# P05_POWER02.net
KiCad netlist of a schematic drawn in Altium Designer
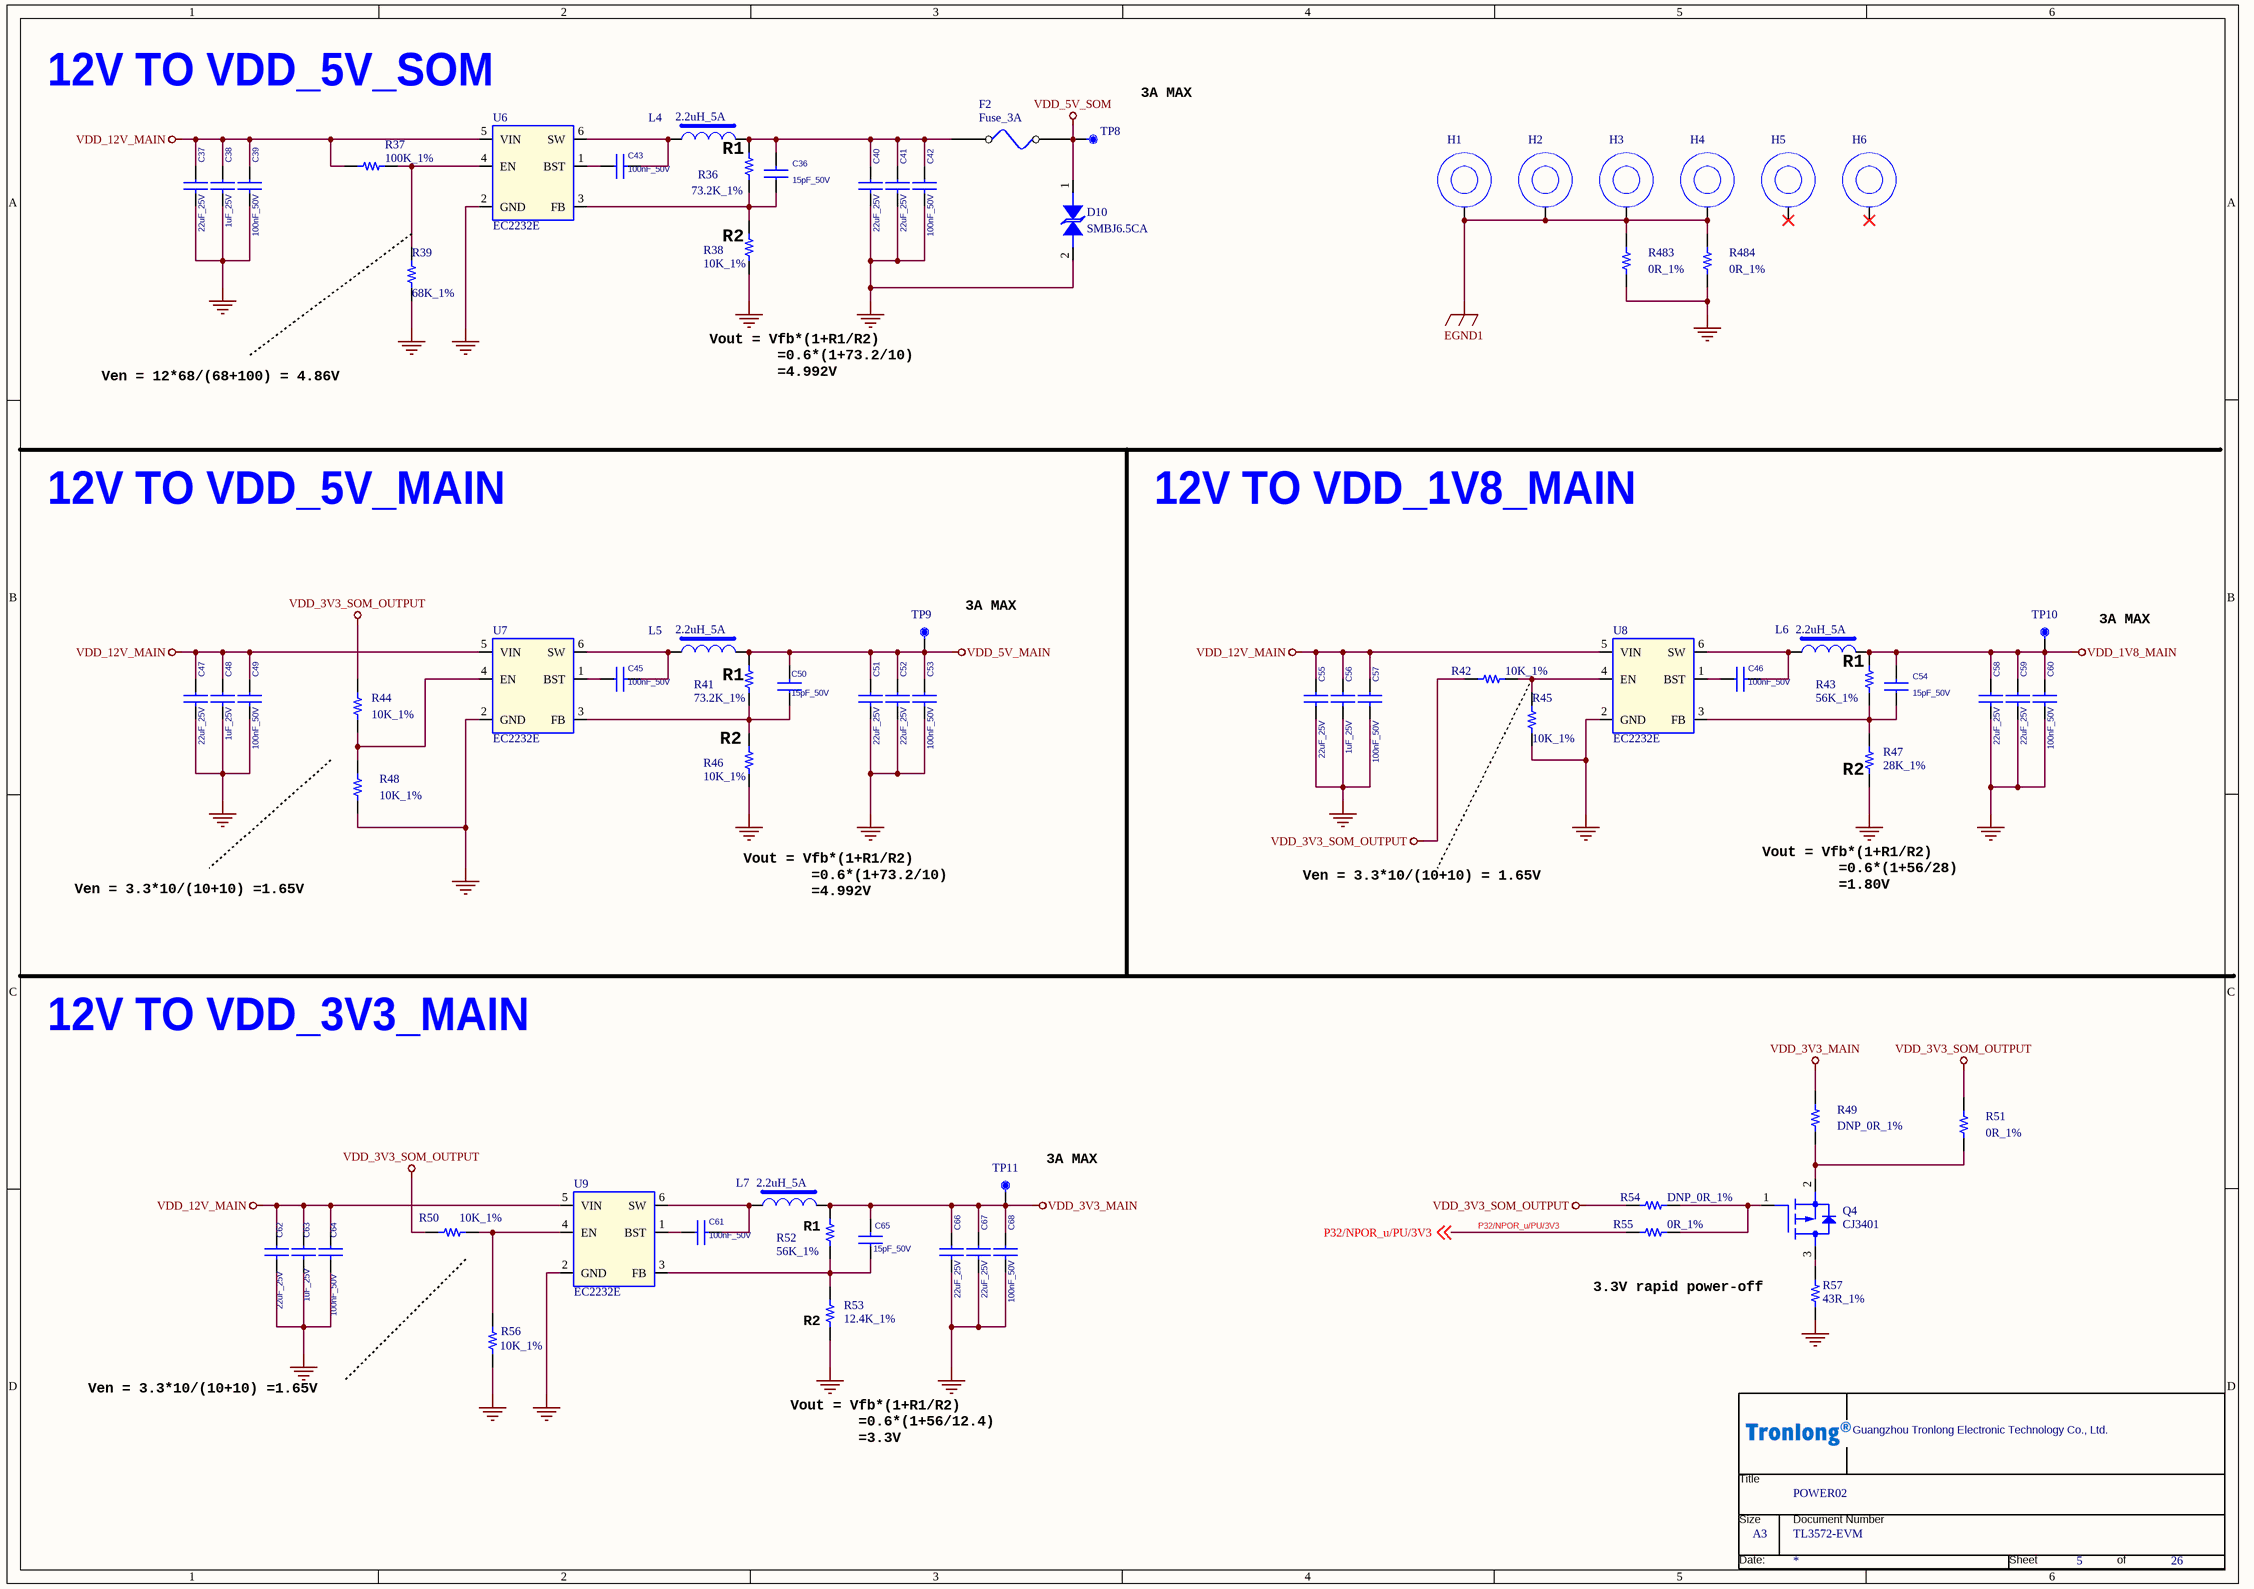
[diagram p0: P05_POWER02.SchDoc]

(export (version "E")
  (design (tool "Eeschema 10.0.6"))
  (components
    (comp (ref "C36")
      (value "15pF_50V")
      (footprint "C0603")
      (description "CL10C150JB8NNNC,CC0603JRNPO9BN150")
      (fields
        (field (name "MANUFACTURER") "广州创龙")
        (field (name "MANUFACTURER PARTNUMBER") "15pF,5%,C0603,50V,（X7R,X5R,COG,NPO或X7S）")
      )
      (libsource (lib "*") (part "CAP NP_Dup2"))
    )
    (comp (ref "C37")
      (value "22uF_25V")
      (footprint "C0805")
      (description "贴片陶瓷电容,22uF,20%,25V,X5R")
      (fields
        (field (name "MANUFACTURER") "广东风华高新科技股份有限公司（FH）")
        (field (name "MANUFACTURER PARTNUMBER") "0805X226M250NT")
      )
      (libsource (lib "*") (part "CAP NP_Dup2"))
    )
    (comp (ref "C38")
      (value "1uF_25V")
      (footprint "C0402")
      (description "贴片陶瓷电容,1uF,10%,25V,X5R")
      (fields
        (field (name "MANUFACTURER PARTNUMBER") "0402X105K250NT")
        (field (name "MANUFACTURER") "广东风华高新科技股份有限公司（FH）")
      )
      (libsource (lib "*") (part "CAP NP_Dup2"))
    )
    (comp (ref "C39")
      (value "100nF_50V")
      (footprint "C0402")
      (description "贴片陶瓷电容,100nF,10%,50V,X7R")
      (fields
        (field (name "MANUFACTURER") "广东风华高新科技股份有限公司（FH）")
        (field (name "MANUFACTURER PARTNUMBER") "0402B104K500NT")
      )
      (libsource (lib "*") (part "CAP NP_Dup2"))
    )
    (comp (ref "C40")
      (value "22uF_25V")
      (footprint "C0805")
      (description "贴片陶瓷电容,22uF,20%,25V,X5R")
      (fields
        (field (name "MANUFACTURER PARTNUMBER") "0805X226M250NT")
        (field (name "MANUFACTURER") "广东风华高新科技股份有限公司（FH）")
      )
      (libsource (lib "*") (part "CAP NP_Dup2"))
    )
    (comp (ref "C41")
      (value "22uF_25V")
      (footprint "C0805")
      (description "贴片陶瓷电容,22uF,20%,25V,X5R")
      (fields
        (field (name "MANUFACTURER PARTNUMBER") "0805X226M250NT")
        (field (name "MANUFACTURER") "广东风华高新科技股份有限公司（FH）")
      )
      (libsource (lib "*") (part "CAP NP_Dup2"))
    )
    (comp (ref "C42")
      (value "100nF_50V")
      (footprint "C0402")
      (description "贴片陶瓷电容,100nF,10%,50V,X7R")
      (fields
        (field (name "MANUFACTURER") "广东风华高新科技股份有限公司（FH）")
        (field (name "MANUFACTURER PARTNUMBER") "0402B104K500NT")
      )
      (libsource (lib "*") (part "CAP NP_Dup2"))
    )
    (comp (ref "C43")
      (value "100nF_50V")
      (footprint "C0402")
      (description "贴片陶瓷电容,100nF,10%,50V,X7R")
      (fields
        (field (name "MANUFACTURER") "广东风华高新科技股份有限公司（FH）")
        (field (name "MANUFACTURER PARTNUMBER") "0402B104K500NT")
      )
      (libsource (lib "*") (part "CAP NP_Dup2"))
    )
    (comp (ref "C45")
      (value "100nF_50V")
      (footprint "C0402")
      (description "贴片陶瓷电容,100nF,10%,50V,X7R")
      (fields
        (field (name "MANUFACTURER PARTNUMBER") "0402B104K500NT")
        (field (name "MANUFACTURER") "广东风华高新科技股份有限公司（FH）")
      )
      (libsource (lib "*") (part "CAP NP_Dup2"))
    )
    (comp (ref "C46")
      (value "100nF_50V")
      (footprint "C0402")
      (description "贴片陶瓷电容,100nF,10%,50V,X7R")
      (fields
        (field (name "MANUFACTURER") "广东风华高新科技股份有限公司（FH）")
        (field (name "MANUFACTURER PARTNUMBER") "0402B104K500NT")
      )
      (libsource (lib "*") (part "CAP NP_Dup2"))
    )
    (comp (ref "C47")
      (value "22uF_25V")
      (footprint "C0805")
      (description "贴片陶瓷电容,22uF,20%,25V,X5R")
      (fields
        (field (name "MANUFACTURER") "广东风华高新科技股份有限公司（FH）")
        (field (name "MANUFACTURER PARTNUMBER") "0805X226M250NT")
      )
      (libsource (lib "*") (part "CAP NP_Dup2"))
    )
    (comp (ref "C48")
      (value "1uF_25V")
      (footprint "C0402")
      (description "贴片陶瓷电容,1uF,10%,25V,X5R")
      (fields
        (field (name "MANUFACTURER PARTNUMBER") "0402X105K250NT")
        (field (name "MANUFACTURER") "广东风华高新科技股份有限公司（FH）")
      )
      (libsource (lib "*") (part "CAP NP_Dup2"))
    )
    (comp (ref "C49")
      (value "100nF_50V")
      (footprint "C0402")
      (description "贴片陶瓷电容,100nF,10%,50V,X7R")
      (fields
        (field (name "MANUFACTURER") "广东风华高新科技股份有限公司（FH）")
        (field (name "MANUFACTURER PARTNUMBER") "0402B104K500NT")
      )
      (libsource (lib "*") (part "CAP NP_Dup2"))
    )
    (comp (ref "C50")
      (value "15pF_50V")
      (footprint "C0603")
      (description "CL10C150JB8NNNC,CC0603JRNPO9BN150")
      (fields
        (field (name "MANUFACTURER") "广州创龙")
        (field (name "MANUFACTURER PARTNUMBER") "15pF,5%,C0603,50V,（X7R,X5R,COG,NPO或X7S）")
      )
      (libsource (lib "*") (part "CAP NP_Dup2"))
    )
    (comp (ref "C51")
      (value "22uF_25V")
      (footprint "C0805")
      (description "贴片陶瓷电容,22uF,20%,25V,X5R")
      (fields
        (field (name "MANUFACTURER PARTNUMBER") "0805X226M250NT")
        (field (name "MANUFACTURER") "广东风华高新科技股份有限公司（FH）")
      )
      (libsource (lib "*") (part "CAP NP_Dup2"))
    )
    (comp (ref "C52")
      (value "22uF_25V")
      (footprint "C0805")
      (description "贴片陶瓷电容,22uF,20%,25V,X5R")
      (fields
        (field (name "MANUFACTURER") "广东风华高新科技股份有限公司（FH）")
        (field (name "MANUFACTURER PARTNUMBER") "0805X226M250NT")
      )
      (libsource (lib "*") (part "CAP NP_Dup2"))
    )
    (comp (ref "C53")
      (value "100nF_50V")
      (footprint "C0402")
      (description "贴片陶瓷电容,100nF,10%,50V,X7R")
      (fields
        (field (name "MANUFACTURER") "广东风华高新科技股份有限公司（FH）")
        (field (name "MANUFACTURER PARTNUMBER") "0402B104K500NT")
      )
      (libsource (lib "*") (part "CAP NP_Dup2"))
    )
    (comp (ref "C54")
      (value "15pF_50V")
      (footprint "C0603")
      (description "CL10C150JB8NNNC,CC0603JRNPO9BN150")
      (fields
        (field (name "MANUFACTURER PARTNUMBER") "15pF,5%,C0603,50V,（X7R,X5R,COG,NPO或X7S）")
        (field (name "MANUFACTURER") "广州创龙")
      )
      (libsource (lib "*") (part "CAP NP_Dup2"))
    )
    (comp (ref "C55")
      (value "22uF_25V")
      (footprint "C0805")
      (description "贴片陶瓷电容,22uF,20%,25V,X5R")
      (fields
        (field (name "MANUFACTURER") "广东风华高新科技股份有限公司（FH）")
        (field (name "MANUFACTURER PARTNUMBER") "0805X226M250NT")
      )
      (libsource (lib "*") (part "CAP NP_Dup2"))
    )
    (comp (ref "C56")
      (value "1uF_25V")
      (footprint "C0402")
      (description "贴片陶瓷电容,1uF,10%,25V,X5R")
      (fields
        (field (name "MANUFACTURER PARTNUMBER") "0402X105K250NT")
        (field (name "MANUFACTURER") "广东风华高新科技股份有限公司（FH）")
      )
      (libsource (lib "*") (part "CAP NP_Dup2"))
    )
    (comp (ref "C57")
      (value "100nF_50V")
      (footprint "C0402")
      (description "贴片陶瓷电容,100nF,10%,50V,X7R")
      (fields
        (field (name "MANUFACTURER PARTNUMBER") "0402B104K500NT")
        (field (name "MANUFACTURER") "广东风华高新科技股份有限公司（FH）")
      )
      (libsource (lib "*") (part "CAP NP_Dup2"))
    )
    (comp (ref "C58")
      (value "22uF_25V")
      (footprint "C0805")
      (description "贴片陶瓷电容,22uF,20%,25V,X5R")
      (fields
        (field (name "MANUFACTURER") "广东风华高新科技股份有限公司（FH）")
        (field (name "MANUFACTURER PARTNUMBER") "0805X226M250NT")
      )
      (libsource (lib "*") (part "CAP NP_Dup2"))
    )
    (comp (ref "C59")
      (value "22uF_25V")
      (footprint "C0805")
      (description "贴片陶瓷电容,22uF,20%,25V,X5R")
      (fields
        (field (name "MANUFACTURER") "广东风华高新科技股份有限公司（FH）")
        (field (name "MANUFACTURER PARTNUMBER") "0805X226M250NT")
      )
      (libsource (lib "*") (part "CAP NP_Dup2"))
    )
    (comp (ref "C60")
      (value "100nF_50V")
      (footprint "C0402")
      (description "贴片陶瓷电容,100nF,10%,50V,X7R")
      (fields
        (field (name "MANUFACTURER PARTNUMBER") "0402B104K500NT")
        (field (name "MANUFACTURER") "广东风华高新科技股份有限公司（FH）")
      )
      (libsource (lib "*") (part "CAP NP_Dup2"))
    )
    (comp (ref "C61")
      (value "100nF_50V")
      (footprint "C0402")
      (description "贴片陶瓷电容,100nF,10%,50V,X7R")
      (fields
        (field (name "MANUFACTURER PARTNUMBER") "0402B104K500NT")
        (field (name "MANUFACTURER") "广东风华高新科技股份有限公司（FH）")
      )
      (libsource (lib "*") (part "CAP NP_Dup2"))
    )
    (comp (ref "C62")
      (value "22uF_25V")
      (footprint "C0805")
      (description "贴片陶瓷电容,22uF,20%,25V,X5R")
      (fields
        (field (name "MANUFACTURER PARTNUMBER") "0805X226M250NT")
        (field (name "MANUFACTURER") "广东风华高新科技股份有限公司（FH）")
      )
      (libsource (lib "*") (part "CAP NP_Dup2"))
    )
    (comp (ref "C63")
      (value "1uF_25V")
      (footprint "C0402")
      (description "贴片陶瓷电容,1uF,10%,25V,X5R")
      (fields
        (field (name "MANUFACTURER PARTNUMBER") "0402X105K250NT")
        (field (name "MANUFACTURER") "广东风华高新科技股份有限公司（FH）")
      )
      (libsource (lib "*") (part "CAP NP_Dup2"))
    )
    (comp (ref "C64")
      (value "100nF_50V")
      (footprint "C0402")
      (description "贴片陶瓷电容,100nF,10%,50V,X7R")
      (fields
        (field (name "MANUFACTURER") "广东风华高新科技股份有限公司（FH）")
        (field (name "MANUFACTURER PARTNUMBER") "0402B104K500NT")
      )
      (libsource (lib "*") (part "CAP NP_Dup2"))
    )
    (comp (ref "C65")
      (value "15pF_50V")
      (footprint "C0603")
      (description "CL10C150JB8NNNC,CC0603JRNPO9BN150")
      (fields
        (field (name "MANUFACTURER") "广州创龙")
        (field (name "MANUFACTURER PARTNUMBER") "15pF,5%,C0603,50V,（X7R,X5R,COG,NPO或X7S）")
      )
      (libsource (lib "*") (part "CAP NP_Dup2"))
    )
    (comp (ref "C66")
      (value "22uF_25V")
      (footprint "C0805")
      (description "贴片陶瓷电容,22uF,20%,25V,X5R")
      (fields
        (field (name "MANUFACTURER PARTNUMBER") "0805X226M250NT")
        (field (name "MANUFACTURER") "广东风华高新科技股份有限公司（FH）")
      )
      (libsource (lib "*") (part "CAP NP_Dup2"))
    )
    (comp (ref "C67")
      (value "22uF_25V")
      (footprint "C0805")
      (description "贴片陶瓷电容,22uF,20%,25V,X5R")
      (fields
        (field (name "MANUFACTURER PARTNUMBER") "0805X226M250NT")
        (field (name "MANUFACTURER") "广东风华高新科技股份有限公司（FH）")
      )
      (libsource (lib "*") (part "CAP NP_Dup2"))
    )
    (comp (ref "C68")
      (value "100nF_50V")
      (footprint "C0402")
      (description "贴片陶瓷电容,100nF,10%,50V,X7R")
      (fields
        (field (name "MANUFACTURER PARTNUMBER") "0402B104K500NT")
        (field (name "MANUFACTURER") "广东风华高新科技股份有限公司（FH）")
      )
      (libsource (lib "*") (part "CAP NP_Dup2"))
    )
    (comp (ref "D10")
      (value "SMBJ6.5CA")
      (footprint "SMB")
      (description "TVS二极管,VRWM=6.5V,VBR=7.22V,一组,双向")
      (fields (field (name "MANUFACTURER") "上海雷卯电子科技有限公司（Leiditech）"))
      (libsource (lib "*") (part "DIODE TVS BI-DIR"))
    )
    (comp (ref "F2")
      (value "Fuse_3A")
      (footprint "F1206")
      (description "保险丝，Vmax=72V,Imax=50A,Ihold=3A")
      (fields
        (field (name "MANUFACTURER") "东莞市竞沃电子科技有限公司（TLC）")
        (field (name "MANUFACTURER PARTNUMBER") "F12T3")
      )
      (libsource (lib "*") (part "FUSE"))
    )
    (comp (ref "H1") (value "HOLE") (footprint "MHOLE_C200D125") (libsource (lib "*") (part "HOLE")))
    (comp (ref "H2") (value "HOLE") (footprint "MHOLE_C200D125") (libsource (lib "*") (part "HOLE")))
    (comp (ref "H3") (value "HOLE") (footprint "MHOLE_C200D125") (libsource (lib "*") (part "HOLE")))
    (comp (ref "H4") (value "HOLE") (footprint "MHOLE_C200D125") (libsource (lib "*") (part "HOLE")))
    (comp (ref "H5") (value "HOLE") (footprint "MHOLE_C200D125") (libsource (lib "*") (part "HOLE")))
    (comp (ref "H6") (value "HOLE") (footprint "MHOLE_C200D125") (libsource (lib "*") (part "HOLE")))
    (comp (ref "L4")
      (value "2.2uH_5A")
      (footprint "SMD-L4040M-2P")
      (description "贴片功率电感,2.2uH,0.048Ω,Isat=7.6A,Irms=5A")
      (fields
        (field (name "MANUFACTURER") "深圳顺络电子股份有限公司（Sunlord）")
        (field (name "MANUFACTURER PARTNUMBER") "WPN4020H2R2MT")
      )
      (libsource (lib "*") (part "INDUCTOR"))
    )
    (comp (ref "L5")
      (value "2.2uH_5A")
      (footprint "SMD-L4040M-2P")
      (description "贴片功率电感,2.2uH,0.048Ω,Isat=7.6A,Irms=5A")
      (fields
        (field (name "MANUFACTURER PARTNUMBER") "WPN4020H2R2MT")
        (field (name "MANUFACTURER") "深圳顺络电子股份有限公司（Sunlord）")
      )
      (libsource (lib "*") (part "INDUCTOR"))
    )
    (comp (ref "L6")
      (value "2.2uH_5A")
      (footprint "SMD-L4040M-2P")
      (description "贴片功率电感,2.2uH,0.048Ω,Isat=7.6A,Irms=5A")
      (fields
        (field (name "MANUFACTURER PARTNUMBER") "WPN4020H2R2MT")
        (field (name "MANUFACTURER") "深圳顺络电子股份有限公司（Sunlord）")
      )
      (libsource (lib "*") (part "INDUCTOR"))
    )
    (comp (ref "L7")
      (value "2.2uH_5A")
      (footprint "SMD-L4040M-2P")
      (description "贴片功率电感,2.2uH,0.048Ω,Isat=7.6A,Irms=5A")
      (fields
        (field (name "MANUFACTURER PARTNUMBER") "WPN4020H2R2MT")
        (field (name "MANUFACTURER") "深圳顺络电子股份有限公司（Sunlord）")
      )
      (libsource (lib "*") (part "INDUCTOR"))
    )
    (comp (ref "Q4")
      (value "CJ3401")
      (footprint "SOT23-3")
      (description "MOSFET,P沟道,VDSS=-30V,VGSS=±12V,ID=-4.2A,PD=0.35W,VGS(th)=-1.3V")
      (fields (field (name "MANUFACTURER") "江苏长晶科技股份有限公司（JSCJ）"))
      (libsource (lib "*") (part "MOSFET P SOT"))
    )
    (comp (ref "R36")
      (value "73.2K_1%")
      (footprint "R0402")
      (description "RC0402FR-0773K2L,0402WGF7322TCE,RTT027322FTH")
      (fields
        (field (name "MANUFACTURER") "广州创龙")
        (field (name "MANUFACTURER PARTNUMBER") "73.2K,±1%,R0402,≥1/16W")
      )
      (libsource (lib "*") (part "Resistor_Dup3"))
    )
    (comp (ref "R37")
      (value "100K_1%")
      (footprint "R0402")
      (description "RC0402FR-07100KL,0402WGF1003TCE")
      (fields
        (field (name "MANUFACTURER") "广州创龙")
        (field (name "MANUFACTURER PARTNUMBER") "100K,±1%,R0402,≥1/16W")
      )
      (libsource (lib "*") (part "Resistor_Dup3"))
    )
    (comp (ref "R38")
      (value "10K_1%")
      (footprint "R0402")
      (description "贴片电阻,10K,±1%,1/16W")
      (fields
        (field (name "MANUFACTURER PARTNUMBER") "RC-02K1002FT")
        (field (name "MANUFACTURER") "广东风华高新科技股份有限公司（FH）")
      )
      (libsource (lib "*") (part "Resistor_Dup3"))
    )
    (comp (ref "R39")
      (value "68K_1%")
      (footprint "R0402")
      (description "贴片电阻,68K,±1%,1/16W")
      (fields
        (field (name "MANUFACTURER PARTNUMBER") "RC-02K6802FT")
        (field (name "MANUFACTURER") "广东风华高新科技股份有限公司（FH）")
      )
      (libsource (lib "*") (part "Resistor_Dup3"))
    )
    (comp (ref "R41")
      (value "73.2K_1%")
      (footprint "R0402")
      (description "RC0402FR-0773K2L,0402WGF7322TCE,RTT027322FTH")
      (fields
        (field (name "MANUFACTURER PARTNUMBER") "73.2K,±1%,R0402,≥1/16W")
        (field (name "MANUFACTURER") "广州创龙")
      )
      (libsource (lib "*") (part "Resistor_Dup3"))
    )
    (comp (ref "R42")
      (value "10K_1%")
      (footprint "R0402")
      (description "贴片电阻,10K,±1%,1/16W")
      (fields
        (field (name "MANUFACTURER PARTNUMBER") "RC-02K1002FT")
        (field (name "MANUFACTURER") "广东风华高新科技股份有限公司（FH）")
      )
      (libsource (lib "*") (part "Resistor_Dup3"))
    )
    (comp (ref "R43")
      (value "56K_1%")
      (footprint "R0402")
      (description "RC0402FR-0756KL，0402WGF5602TCE")
      (fields
        (field (name "MANUFACTURER") "广州创龙")
        (field (name "MANUFACTURER PARTNUMBER") "56K,±1%,R0402,≥1/16W")
      )
      (libsource (lib "*") (part "Resistor_Dup3"))
    )
    (comp (ref "R44")
      (value "10K_1%")
      (footprint "R0402")
      (description "贴片电阻,10K,±1%,1/16W")
      (fields
        (field (name "MANUFACTURER PARTNUMBER") "RC-02K1002FT")
        (field (name "MANUFACTURER") "广东风华高新科技股份有限公司（FH）")
      )
      (libsource (lib "*") (part "Resistor_Dup3"))
    )
    (comp (ref "R45")
      (value "10K_1%")
      (footprint "R0402")
      (description "贴片电阻,10K,±1%,1/16W")
      (fields
        (field (name "MANUFACTURER PARTNUMBER") "RC-02K1002FT")
        (field (name "MANUFACTURER") "广东风华高新科技股份有限公司（FH）")
      )
      (libsource (lib "*") (part "Resistor_Dup3"))
    )
    (comp (ref "R46")
      (value "10K_1%")
      (footprint "R0402")
      (description "贴片电阻,10K,±1%,1/16W")
      (fields
        (field (name "MANUFACTURER PARTNUMBER") "RC-02K1002FT")
        (field (name "MANUFACTURER") "广东风华高新科技股份有限公司（FH）")
      )
      (libsource (lib "*") (part "Resistor_Dup3"))
    )
    (comp (ref "R47")
      (value "28K_1%")
      (footprint "R0402")
      (description "贴片电阻,28K,±1%,1/16W")
      (fields
        (field (name "MANUFACTURER PARTNUMBER") "RC-02K2802FT")
        (field (name "MANUFACTURER") "广东风华高新科技股份有限公司（FH）")
      )
      (libsource (lib "*") (part "Resistor_Dup3"))
    )
    (comp (ref "R48")
      (value "10K_1%")
      (footprint "R0402")
      (description "贴片电阻,10K,±1%,1/16W")
      (fields
        (field (name "MANUFACTURER PARTNUMBER") "RC-02K1002FT")
        (field (name "MANUFACTURER") "广东风华高新科技股份有限公司（FH）")
      )
      (libsource (lib "*") (part "Resistor_Dup3"))
    )
    (comp (ref "R49")
      (value "DNP_0R_1%")
      (footprint "R0603")
      (description "贴片电阻,0R,±1%,1/10W")
      (fields
        (field (name "MANUFACTURER PARTNUMBER") "RS-03000FT")
        (field (name "MANUFACTURER") "广东风华高新科技股份有限公司（FH）")
      )
      (libsource (lib "*") (part "Resistor_Dup3"))
    )
    (comp (ref "R50")
      (value "10K_1%")
      (footprint "R0402")
      (description "贴片电阻,10K,±1%,1/16W")
      (fields
        (field (name "MANUFACTURER PARTNUMBER") "RC-02K1002FT")
        (field (name "MANUFACTURER") "广东风华高新科技股份有限公司（FH）")
      )
      (libsource (lib "*") (part "Resistor_Dup3"))
    )
    (comp (ref "R51")
      (value "0R_1%")
      (footprint "R0603")
      (description "贴片电阻,0R,±1%,1/10W")
      (fields
        (field (name "MANUFACTURER") "广东风华高新科技股份有限公司（FH）")
        (field (name "MANUFACTURER PARTNUMBER") "RS-03000FT")
      )
      (libsource (lib "*") (part "Resistor_Dup3"))
    )
    (comp (ref "R52")
      (value "56K_1%")
      (footprint "R0402")
      (description "RC0402FR-0756KL，0402WGF5602TCE")
      (fields
        (field (name "MANUFACTURER PARTNUMBER") "56K,±1%,R0402,≥1/16W")
        (field (name "MANUFACTURER") "广州创龙")
      )
      (libsource (lib "*") (part "Resistor_Dup3"))
    )
    (comp (ref "R53")
      (value "12.4K_1%")
      (footprint "R0402")
      (description "0402WGF1242TCE")
      (fields
        (field (name "MANUFACTURER PARTNUMBER") "12.4K,±1%,R0402,≥1/16W")
        (field (name "MANUFACTURER") "广州创龙")
      )
      (libsource (lib "*") (part "Resistor_Dup3"))
    )
    (comp (ref "R54")
      (value "DNP_0R_1%")
      (footprint "R0402")
      (description "贴片电阻,0R,±1%,1/16W")
      (fields
        (field (name "MANUFACTURER") "广东风华高新科技股份有限公司（FH）")
        (field (name "MANUFACTURER PARTNUMBER") "RC-02000FT")
      )
      (libsource (lib "*") (part "Resistor_Dup3"))
    )
    (comp (ref "R55")
      (value "0R_1%")
      (footprint "R0402")
      (description "贴片电阻,0R,±1%,1/16W")
      (fields
        (field (name "MANUFACTURER") "广东风华高新科技股份有限公司（FH）")
        (field (name "MANUFACTURER PARTNUMBER") "RC-02000FT")
      )
      (libsource (lib "*") (part "Resistor_Dup3"))
    )
    (comp (ref "R56")
      (value "10K_1%")
      (footprint "R0402")
      (description "贴片电阻,10K,±1%,1/16W")
      (fields
        (field (name "MANUFACTURER") "广东风华高新科技股份有限公司（FH）")
        (field (name "MANUFACTURER PARTNUMBER") "RC-02K1002FT")
      )
      (libsource (lib "*") (part "Resistor_Dup3"))
    )
    (comp (ref "R57")
      (value "43R_1%")
      (footprint "R0805")
      (description "贴片电阻,43R,±1%,1/8W")
      (fields
        (field (name "MANUFACTURER PARTNUMBER") "RS-05K43R0FT")
        (field (name "MANUFACTURER") "广东风华高新科技股份有限公司（FH）")
      )
      (libsource (lib "*") (part "Resistor_Dup3"))
    )
    (comp (ref "R483")
      (value "0R_1%")
      (footprint "R1206")
      (description "贴片电阻,0R,±1%,1/4W")
      (fields
        (field (name "MANUFACTURER") "广东风华高新科技股份有限公司（FH）")
        (field (name "MANUFACTURER PARTNUMBER") "RS-06000FT")
      )
      (libsource (lib "*") (part "Resistor_Dup3"))
    )
    (comp (ref "R484")
      (value "0R_1%")
      (footprint "R1206")
      (description "贴片电阻,0R,±1%,1/4W")
      (fields
        (field (name "MANUFACTURER PARTNUMBER") "RS-06000FT")
        (field (name "MANUFACTURER") "广东风华高新科技股份有限公司（FH）")
      )
      (libsource (lib "*") (part "Resistor_Dup3"))
    )
    (comp (ref "TP8")
      (value "SMT TP")
      (footprint "TP30")
      (description "/")
      (libsource (lib "*") (part "TP-S40"))
    )
    (comp (ref "TP9")
      (value "SMT TP")
      (footprint "TP30")
      (description "/")
      (libsource (lib "*") (part "TP-S40"))
    )
    (comp (ref "TP10")
      (value "SMT TP")
      (footprint "TP30")
      (description "/")
      (libsource (lib "*") (part "TP-S40"))
    )
    (comp (ref "TP11")
      (value "SMT TP")
      (footprint "TP30")
      (description "/")
      (libsource (lib "*") (part "TP-S40"))
    )
    (comp (ref "U6")
      (value "EC2232E")
      (footprint "SOT-23-6L")
      (description "DC/DC,Buck,Vin:4.5V~17V,Vout:0.6V~6V,3A,1路")
      (fields (field (name "MANUFACTURER") "上海芯强微电子股份有限公司（Ecranic）"))
      (libsource (lib "*") (part "WD1304E30"))
    )
    (comp (ref "U7")
      (value "EC2232E")
      (footprint "SOT-23-6L")
      (description "DC/DC,Buck,Vin:4.5V~17V,Vout:0.6V~6V,3A,1路")
      (fields (field (name "MANUFACTURER") "上海芯强微电子股份有限公司（Ecranic）"))
      (libsource (lib "*") (part "WD1304E30"))
    )
    (comp (ref "U8")
      (value "EC2232E")
      (footprint "SOT-23-6L")
      (description "DC/DC,Buck,Vin:4.5V~17V,Vout:0.6V~6V,3A,1路")
      (fields (field (name "MANUFACTURER") "上海芯强微电子股份有限公司（Ecranic）"))
      (libsource (lib "*") (part "WD1304E30_0_Dup1"))
    )
    (comp (ref "U9")
      (value "EC2232E")
      (footprint "SOT-23-6L")
      (description "DC/DC,Buck,Vin:4.5V~17V,Vout:0.6V~6V,3A,1路")
      (fields (field (name "MANUFACTURER") "上海芯强微电子股份有限公司（Ecranic）"))
      (libsource (lib "*") (part "WD1304E30"))
    )
  )
  (nets
    (net (code "1") (name "EGND1") (class "Default")
      (node (ref "H1") (pin "1") (pinfunction "1_1") (pintype "passive"))
      (node (ref "H2") (pin "1") (pinfunction "1_1") (pintype "passive"))
      (node (ref "H3") (pin "1") (pinfunction "1_1") (pintype "passive"))
      (node (ref "H4") (pin "1") (pinfunction "1_1") (pintype "passive"))
      (node (ref "R483") (pin "2") (pinfunction "2_2") (pintype "passive"))
      (node (ref "R484") (pin "2") (pinfunction "2_2") (pintype "passive"))
    )
    (net (code "2") (name "GND") (class "Default")
      (node (ref "C37") (pin "2") (pinfunction "2_2") (pintype "passive"))
      (node (ref "C38") (pin "2") (pinfunction "2_2") (pintype "passive"))
      (node (ref "C39") (pin "2") (pinfunction "2_2") (pintype "passive"))
      (node (ref "C40") (pin "2") (pinfunction "2_2") (pintype "passive"))
      (node (ref "C41") (pin "2") (pinfunction "2_2") (pintype "passive"))
      (node (ref "C42") (pin "2") (pinfunction "2_2") (pintype "passive"))
      (node (ref "C47") (pin "2") (pinfunction "2_2") (pintype "passive"))
      (node (ref "C48") (pin "2") (pinfunction "2_2") (pintype "passive"))
      (node (ref "C49") (pin "2") (pinfunction "2_2") (pintype "passive"))
      (node (ref "C51") (pin "2") (pinfunction "2_2") (pintype "passive"))
      (node (ref "C52") (pin "2") (pinfunction "2_2") (pintype "passive"))
      (node (ref "C53") (pin "2") (pinfunction "2_2") (pintype "passive"))
      (node (ref "C55") (pin "2") (pinfunction "2_2") (pintype "passive"))
      (node (ref "C56") (pin "2") (pinfunction "2_2") (pintype "passive"))
      (node (ref "C57") (pin "2") (pinfunction "2_2") (pintype "passive"))
      (node (ref "C58") (pin "2") (pinfunction "2_2") (pintype "passive"))
      (node (ref "C59") (pin "2") (pinfunction "2_2") (pintype "passive"))
      (node (ref "C60") (pin "2") (pinfunction "2_2") (pintype "passive"))
      (node (ref "C62") (pin "2") (pinfunction "2_2") (pintype "passive"))
      (node (ref "C63") (pin "2") (pinfunction "2_2") (pintype "passive"))
      (node (ref "C64") (pin "2") (pinfunction "2_2") (pintype "passive"))
      (node (ref "C66") (pin "2") (pinfunction "2_2") (pintype "passive"))
      (node (ref "C67") (pin "2") (pinfunction "2_2") (pintype "passive"))
      (node (ref "C68") (pin "2") (pinfunction "2_2") (pintype "passive"))
      (node (ref "D10") (pin "2") (pinfunction "2_2") (pintype "passive"))
      (node (ref "R38") (pin "1") (pinfunction "1_1") (pintype "passive"))
      (node (ref "R39") (pin "1") (pinfunction "1_1") (pintype "passive"))
      (node (ref "R45") (pin "1") (pinfunction "1_1") (pintype "passive"))
      (node (ref "R46") (pin "1") (pinfunction "1_1") (pintype "passive"))
      (node (ref "R47") (pin "1") (pinfunction "1_1") (pintype "passive"))
      (node (ref "R48") (pin "1") (pinfunction "1_1") (pintype "passive"))
      (node (ref "R483") (pin "1") (pinfunction "1_1") (pintype "passive"))
      (node (ref "R484") (pin "1") (pinfunction "1_1") (pintype "passive"))
      (node (ref "R53") (pin "1") (pinfunction "1_1") (pintype "passive"))
      (node (ref "R56") (pin "1") (pinfunction "1_1") (pintype "passive"))
      (node (ref "R57") (pin "2") (pinfunction "2_2") (pintype "passive"))
      (node (ref "U6") (pin "2") (pinfunction "GND_2") (pintype "power_in"))
      (node (ref "U7") (pin "2") (pinfunction "GND_2") (pintype "power_in"))
      (node (ref "U8") (pin "2") (pinfunction "GND_2") (pintype "power_in"))
      (node (ref "U9") (pin "2") (pinfunction "GND_2") (pintype "power_in"))
    )
    (net (code "3") (name "Net-(C36-Pad2)") (class "Default")
      (node (ref "C36") (pin "2") (pinfunction "2_2") (pintype "passive"))
      (node (ref "C40") (pin "1") (pinfunction "1_1") (pintype "passive"))
      (node (ref "C41") (pin "1") (pinfunction "1_1") (pintype "passive"))
      (node (ref "C42") (pin "1") (pinfunction "1_1") (pintype "passive"))
      (node (ref "F2") (pin "1") (pinfunction "1_1") (pintype "passive"))
      (node (ref "L4") (pin "2") (pinfunction "2_2") (pintype "passive"))
      (node (ref "R36") (pin "2") (pinfunction "2_2") (pintype "passive"))
    )
    (net (code "4") (name "Net-(Q4-DRAIN)") (class "Default")
      (node (ref "Q4") (pin "3") (pinfunction "DRAIN_3") (pintype "passive"))
      (node (ref "R57") (pin "1") (pinfunction "1_1") (pintype "passive"))
    )
    (net (code "5") (name "Net-(Q4-GATE)") (class "Default")
      (node (ref "Q4") (pin "1") (pinfunction "GATE_1") (pintype "passive"))
      (node (ref "R54") (pin "1") (pinfunction "1_1") (pintype "passive"))
      (node (ref "R55") (pin "1") (pinfunction "1_1") (pintype "passive"))
    )
    (net (code "6") (name "Net-(Q4-SOURCE)") (class "Default")
      (node (ref "Q4") (pin "2") (pinfunction "SOURCE_2") (pintype "passive"))
      (node (ref "R49") (pin "1") (pinfunction "1_1") (pintype "passive"))
      (node (ref "R51") (pin "1") (pinfunction "1_1") (pintype "passive"))
    )
    (net (code "7") (name "Net-(U6-BST)") (class "Default")
      (node (ref "C43") (pin "1") (pinfunction "1_1") (pintype "passive"))
      (node (ref "U6") (pin "1") (pinfunction "BST_1") (pintype "passive"))
    )
    (net (code "8") (name "Net-(U6-EN)") (class "Default")
      (node (ref "R37") (pin "2") (pinfunction "2_2") (pintype "passive"))
      (node (ref "R39") (pin "2") (pinfunction "2_2") (pintype "passive"))
      (node (ref "U6") (pin "4") (pinfunction "EN_4") (pintype "passive"))
    )
    (net (code "9") (name "Net-(U6-FB)") (class "Default")
      (node (ref "C36") (pin "1") (pinfunction "1_1") (pintype "passive"))
      (node (ref "R36") (pin "1") (pinfunction "1_1") (pintype "passive"))
      (node (ref "R38") (pin "2") (pinfunction "2_2") (pintype "passive"))
      (node (ref "U6") (pin "3") (pinfunction "FB_3") (pintype "passive"))
    )
    (net (code "10") (name "Net-(U6-SW)") (class "Default")
      (node (ref "C43") (pin "2") (pinfunction "2_2") (pintype "passive"))
      (node (ref "L4") (pin "1") (pinfunction "1_1") (pintype "passive"))
      (node (ref "U6") (pin "6") (pinfunction "SW_6") (pintype "passive"))
    )
    (net (code "11") (name "Net-(U7-BST)") (class "Default")
      (node (ref "C45") (pin "1") (pinfunction "1_1") (pintype "passive"))
      (node (ref "U7") (pin "1") (pinfunction "BST_1") (pintype "passive"))
    )
    (net (code "12") (name "Net-(U7-EN)") (class "Default")
      (node (ref "R44") (pin "1") (pinfunction "1_1") (pintype "passive"))
      (node (ref "R48") (pin "2") (pinfunction "2_2") (pintype "passive"))
      (node (ref "U7") (pin "4") (pinfunction "EN_4") (pintype "passive"))
    )
    (net (code "13") (name "Net-(U7-FB)") (class "Default")
      (node (ref "C50") (pin "1") (pinfunction "1_1") (pintype "passive"))
      (node (ref "R41") (pin "1") (pinfunction "1_1") (pintype "passive"))
      (node (ref "R46") (pin "2") (pinfunction "2_2") (pintype "passive"))
      (node (ref "U7") (pin "3") (pinfunction "FB_3") (pintype "passive"))
    )
    (net (code "14") (name "Net-(U7-SW)") (class "Default")
      (node (ref "C45") (pin "2") (pinfunction "2_2") (pintype "passive"))
      (node (ref "L5") (pin "1") (pinfunction "1_1") (pintype "passive"))
      (node (ref "U7") (pin "6") (pinfunction "SW_6") (pintype "passive"))
    )
    (net (code "15") (name "Net-(U8-BST)") (class "Default")
      (node (ref "C46") (pin "1") (pinfunction "1_1") (pintype "passive"))
      (node (ref "U8") (pin "1") (pinfunction "BST_1") (pintype "passive"))
    )
    (net (code "16") (name "Net-(U8-EN)") (class "Default")
      (node (ref "R42") (pin "2") (pinfunction "2_2") (pintype "passive"))
      (node (ref "R45") (pin "2") (pinfunction "2_2") (pintype "passive"))
      (node (ref "U8") (pin "4") (pinfunction "EN_4") (pintype "passive"))
    )
    (net (code "17") (name "Net-(U8-FB)") (class "Default")
      (node (ref "C54") (pin "1") (pinfunction "1_1") (pintype "passive"))
      (node (ref "R43") (pin "1") (pinfunction "1_1") (pintype "passive"))
      (node (ref "R47") (pin "2") (pinfunction "2_2") (pintype "passive"))
      (node (ref "U8") (pin "3") (pinfunction "FB_3") (pintype "passive"))
    )
    (net (code "18") (name "Net-(U8-SW)") (class "Default")
      (node (ref "C46") (pin "2") (pinfunction "2_2") (pintype "passive"))
      (node (ref "L6") (pin "1") (pinfunction "1_1") (pintype "passive"))
      (node (ref "U8") (pin "6") (pinfunction "SW_6") (pintype "passive"))
    )
    (net (code "19") (name "Net-(U9-BST)") (class "Default")
      (node (ref "C61") (pin "1") (pinfunction "1_1") (pintype "passive"))
      (node (ref "U9") (pin "1") (pinfunction "BST_1") (pintype "passive"))
    )
    (net (code "20") (name "Net-(U9-EN)") (class "Default")
      (node (ref "R50") (pin "1") (pinfunction "1_1") (pintype "passive"))
      (node (ref "R56") (pin "2") (pinfunction "2_2") (pintype "passive"))
      (node (ref "U9") (pin "4") (pinfunction "EN_4") (pintype "passive"))
    )
    (net (code "21") (name "Net-(U9-FB)") (class "Default")
      (node (ref "C65") (pin "1") (pinfunction "1_1") (pintype "passive"))
      (node (ref "R52") (pin "1") (pinfunction "1_1") (pintype "passive"))
      (node (ref "R53") (pin "2") (pinfunction "2_2") (pintype "passive"))
      (node (ref "U9") (pin "3") (pinfunction "FB_3") (pintype "passive"))
    )
    (net (code "22") (name "Net-(U9-SW)") (class "Default")
      (node (ref "C61") (pin "2") (pinfunction "2_2") (pintype "passive"))
      (node (ref "L7") (pin "1") (pinfunction "1_1") (pintype "passive"))
      (node (ref "U9") (pin "6") (pinfunction "SW_6") (pintype "passive"))
    )
    (net (code "23") (name "P32{slash}NPOR_u{slash}PU{slash}3V3") (class "Default")
      (node (ref "R55") (pin "2") (pinfunction "2_2") (pintype "passive"))
    )
    (net (code "24") (name "VDD_1V8_MAIN") (class "Default")
      (node (ref "C54") (pin "2") (pinfunction "2_2") (pintype "passive"))
      (node (ref "C58") (pin "1") (pinfunction "1_1") (pintype "passive"))
      (node (ref "C59") (pin "1") (pinfunction "1_1") (pintype "passive"))
      (node (ref "C60") (pin "1") (pinfunction "1_1") (pintype "passive"))
      (node (ref "L6") (pin "2") (pinfunction "2_2") (pintype "passive"))
      (node (ref "R43") (pin "2") (pinfunction "2_2") (pintype "passive"))
      (node (ref "TP10") (pin "1") (pinfunction "1_1") (pintype "passive"))
    )
    (net (code "25") (name "VDD_3V3_MAIN") (class "Default")
      (node (ref "C65") (pin "2") (pinfunction "2_2") (pintype "passive"))
      (node (ref "C66") (pin "1") (pinfunction "1_1") (pintype "passive"))
      (node (ref "C67") (pin "1") (pinfunction "1_1") (pintype "passive"))
      (node (ref "C68") (pin "1") (pinfunction "1_1") (pintype "passive"))
      (node (ref "L7") (pin "2") (pinfunction "2_2") (pintype "passive"))
      (node (ref "R49") (pin "2") (pinfunction "2_2") (pintype "passive"))
      (node (ref "R52") (pin "2") (pinfunction "2_2") (pintype "passive"))
      (node (ref "TP11") (pin "1") (pinfunction "1_1") (pintype "passive"))
    )
    (net (code "26") (name "VDD_3V3_SOM_OUTPUT") (class "Default")
      (node (ref "R42") (pin "1") (pinfunction "1_1") (pintype "passive"))
      (node (ref "R44") (pin "2") (pinfunction "2_2") (pintype "passive"))
      (node (ref "R50") (pin "2") (pinfunction "2_2") (pintype "passive"))
      (node (ref "R51") (pin "2") (pinfunction "2_2") (pintype "passive"))
      (node (ref "R54") (pin "2") (pinfunction "2_2") (pintype "passive"))
    )
    (net (code "27") (name "VDD_5V_MAIN") (class "Default")
      (node (ref "C50") (pin "2") (pinfunction "2_2") (pintype "passive"))
      (node (ref "C51") (pin "1") (pinfunction "1_1") (pintype "passive"))
      (node (ref "C52") (pin "1") (pinfunction "1_1") (pintype "passive"))
      (node (ref "C53") (pin "1") (pinfunction "1_1") (pintype "passive"))
      (node (ref "L5") (pin "2") (pinfunction "2_2") (pintype "passive"))
      (node (ref "R41") (pin "2") (pinfunction "2_2") (pintype "passive"))
      (node (ref "TP9") (pin "1") (pinfunction "1_1") (pintype "passive"))
    )
    (net (code "28") (name "VDD_5V_SOM") (class "Default")
      (node (ref "D10") (pin "1") (pinfunction "1_1") (pintype "passive"))
      (node (ref "F2") (pin "2") (pinfunction "2_2") (pintype "passive"))
      (node (ref "TP8") (pin "1") (pinfunction "1_1") (pintype "passive"))
    )
    (net (code "29") (name "VDD_12V_MAIN") (class "Default")
      (node (ref "C37") (pin "1") (pinfunction "1_1") (pintype "passive"))
      (node (ref "C38") (pin "1") (pinfunction "1_1") (pintype "passive"))
      (node (ref "C39") (pin "1") (pinfunction "1_1") (pintype "passive"))
      (node (ref "C47") (pin "1") (pinfunction "1_1") (pintype "passive"))
      (node (ref "C48") (pin "1") (pinfunction "1_1") (pintype "passive"))
      (node (ref "C49") (pin "1") (pinfunction "1_1") (pintype "passive"))
      (node (ref "C55") (pin "1") (pinfunction "1_1") (pintype "passive"))
      (node (ref "C56") (pin "1") (pinfunction "1_1") (pintype "passive"))
      (node (ref "C57") (pin "1") (pinfunction "1_1") (pintype "passive"))
      (node (ref "C62") (pin "1") (pinfunction "1_1") (pintype "passive"))
      (node (ref "C63") (pin "1") (pinfunction "1_1") (pintype "passive"))
      (node (ref "C64") (pin "1") (pinfunction "1_1") (pintype "passive"))
      (node (ref "R37") (pin "1") (pinfunction "1_1") (pintype "passive"))
      (node (ref "U6") (pin "5") (pinfunction "VIN_5") (pintype "power_in"))
      (node (ref "U7") (pin "5") (pinfunction "VIN_5") (pintype "power_in"))
      (node (ref "U8") (pin "5") (pinfunction "VIN_5") (pintype "power_in"))
      (node (ref "U9") (pin "5") (pinfunction "VIN_5") (pintype "power_in"))
    )
    (net (code "30") (name "unconnected-(H5-Pad1)") (class "Default")
      (node (ref "H5") (pin "1") (pinfunction "1_1") (pintype "passive+no_connect"))
    )
    (net (code "31") (name "unconnected-(H6-Pad1)") (class "Default")
      (node (ref "H6") (pin "1") (pinfunction "1_1") (pintype "passive+no_connect"))
    )
  )
)
